# Temperature-Humidity.net
KiCad netlist of a schematic drawn in EAGLE
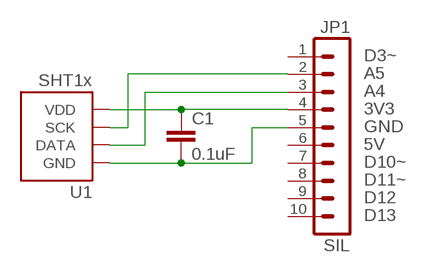
[diagram p0: schematic, sheet 1]

(export (version "E")
  (design (tool "Eeschema 10.0.6"))
  (components
    (comp (ref "C1")
      (value "0.1uF")
      (footprint "eagle-import:0603-CAP")
      (libsource (lib "eagle-import") (part "CAP0603-CAP"))
    )
    (comp (ref "JP1")
      (value "SIL")
      (footprint "eagle-import:SIL-1X10")
      (fields (field (name "MANUFACTURER") "FCI") (field (name "PART_NUMBER") "77315-818-36LF "))
      (libsource (lib "eagle-import") (part "1X10-SIL-CONNECTOR"))
    )
    (comp (ref "U1")
      (value "SHT1x")
      (footprint "eagle-import:SHT1X")
      (libsource (lib "eagle-import") (part "SHT1XSMD"))
    )
  )
  (nets
    (net (code "1") (name "Net-(U1-DATA)") (class "Default")
      (node (ref "JP1") (pin "3") (pinfunction "3_3") (pintype "passive"))
      (node (ref "U1") (pin "2") (pinfunction "DATA_2") (pintype "bidirectional"))
    )
    (net (code "2") (name "Net-(U1-GND)") (class "Default")
      (node (ref "C1") (pin "2") (pinfunction "2_2") (pintype "passive"))
      (node (ref "JP1") (pin "5") (pinfunction "5_5") (pintype "passive"))
      (node (ref "U1") (pin "1") (pinfunction "GND_1") (pintype "power_in"))
    )
    (net (code "3") (name "Net-(U1-SCK)") (class "Default")
      (node (ref "JP1") (pin "2") (pinfunction "2_2") (pintype "passive"))
      (node (ref "U1") (pin "3") (pinfunction "SCK_3") (pintype "input"))
    )
    (net (code "4") (name "Net-(U1-VDD)") (class "Default")
      (node (ref "C1") (pin "1") (pinfunction "1_1") (pintype "passive"))
      (node (ref "JP1") (pin "4") (pinfunction "4_4") (pintype "passive"))
      (node (ref "U1") (pin "4") (pinfunction "VDD_4") (pintype "power_in"))
    )
    (net (code "5") (name "unconnected-(JP1-Pad1)") (class "Default")
      (node (ref "JP1") (pin "1") (pinfunction "1_1") (pintype "passive"))
    )
    (net (code "6") (name "unconnected-(JP1-Pad6)") (class "Default")
      (node (ref "JP1") (pin "6") (pinfunction "6_6") (pintype "passive"))
    )
    (net (code "7") (name "unconnected-(JP1-Pad7)") (class "Default")
      (node (ref "JP1") (pin "7") (pinfunction "7_7") (pintype "passive"))
    )
    (net (code "8") (name "unconnected-(JP1-Pad8)") (class "Default")
      (node (ref "JP1") (pin "8") (pinfunction "8_8") (pintype "passive"))
    )
    (net (code "9") (name "unconnected-(JP1-Pad9)") (class "Default")
      (node (ref "JP1") (pin "9") (pinfunction "9_9") (pintype "passive"))
    )
    (net (code "10") (name "unconnected-(JP1-Pad10)") (class "Default")
      (node (ref "JP1") (pin "10") (pinfunction "10_10") (pintype "passive"))
    )
  )
)
